# 18_LPDDR4_LPDDR4x_2.net
KiCad netlist of a schematic drawn in Altium Designer
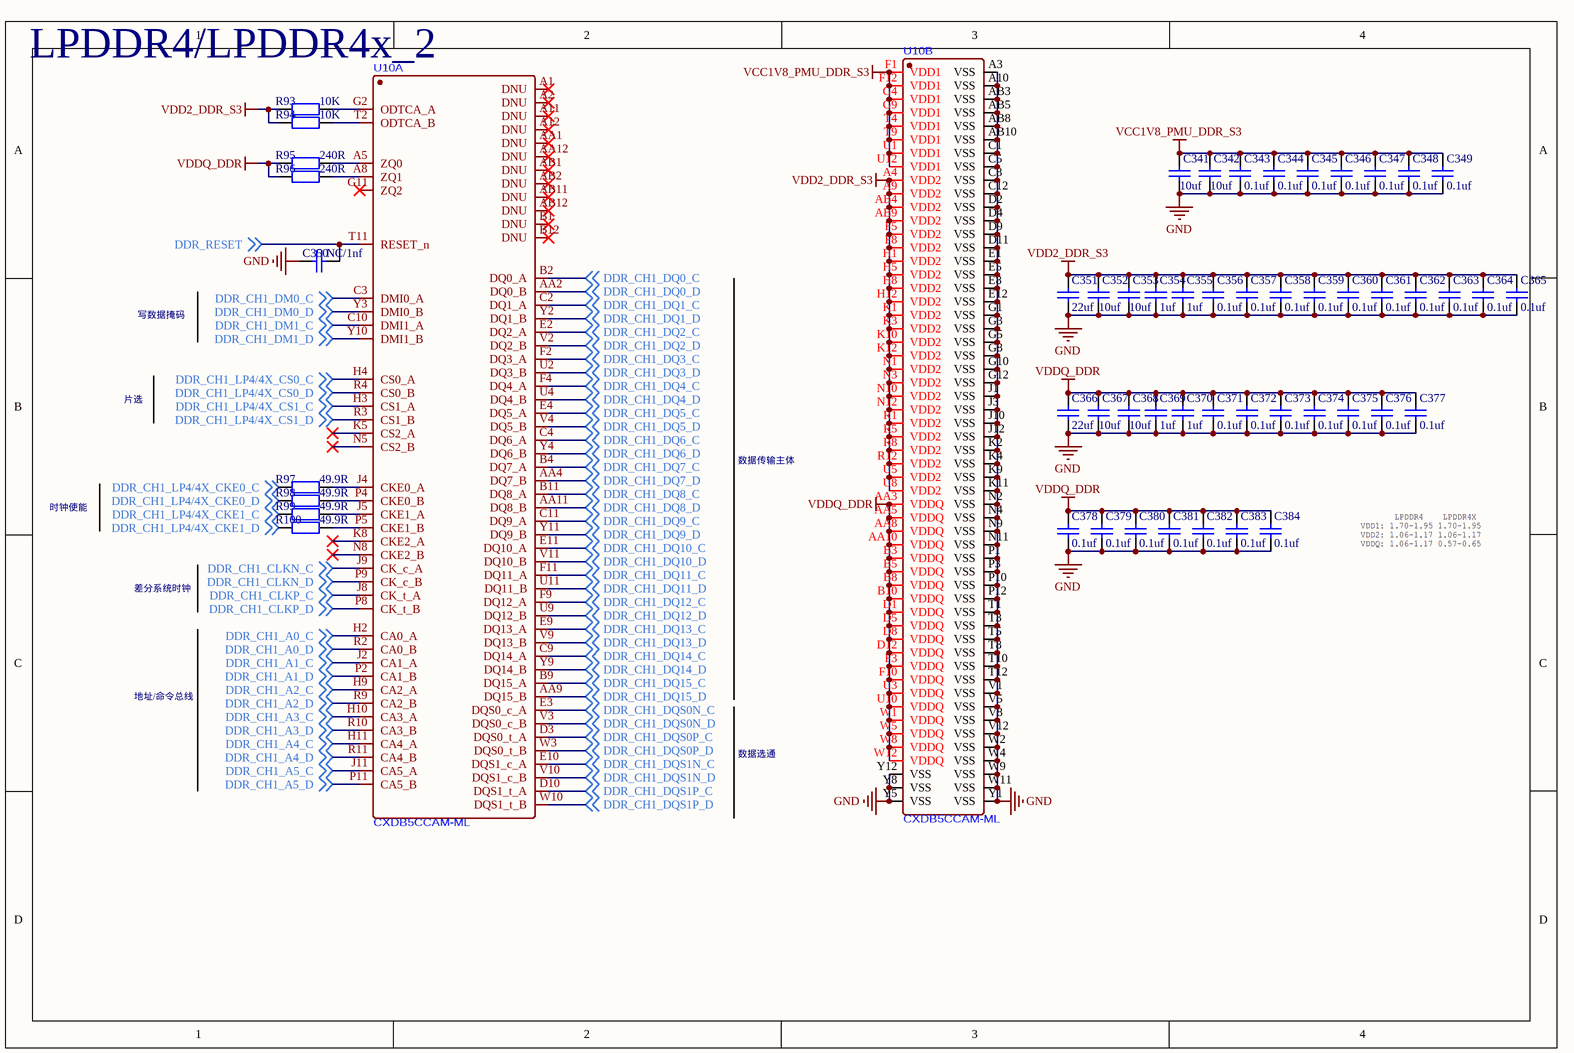
[diagram p0: 18.LPDDR4_LPDDR4x_2.SchDoc]

(export (version "E")
  (design (tool "Eeschema 10.0.6"))
  (components
    (comp (ref "C341")
      (value "10uf")
      (footprint "0.PCB1:C0402_L")
      (description "贴片电容/MLCC电容")
      (libsource (lib "RK3588") (part "C"))
    )
    (comp (ref "C342")
      (value "10uf")
      (footprint "0.PCB1:C0402_L")
      (description "贴片电容/MLCC电容")
      (libsource (lib "RK3588") (part "C"))
    )
    (comp (ref "C343")
      (value "0.1uf")
      (footprint "0.PCB1:C0201_L")
      (description "贴片电容/MLCC电容")
      (libsource (lib "RK3588") (part "C"))
    )
    (comp (ref "C344")
      (value "0.1uf")
      (footprint "0.PCB1:C0201_L")
      (description "贴片电容/MLCC电容")
      (libsource (lib "RK3588") (part "C"))
    )
    (comp (ref "C345")
      (value "0.1uf")
      (footprint "0.PCB1:C0201_L")
      (description "贴片电容/MLCC电容")
      (libsource (lib "RK3588") (part "C"))
    )
    (comp (ref "C346")
      (value "0.1uf")
      (footprint "0.PCB1:C0201_L")
      (description "贴片电容/MLCC电容")
      (libsource (lib "RK3588") (part "C"))
    )
    (comp (ref "C347")
      (value "0.1uf")
      (footprint "0.PCB1:C0201_L")
      (description "贴片电容/MLCC电容")
      (libsource (lib "RK3588") (part "C"))
    )
    (comp (ref "C348")
      (value "0.1uf")
      (footprint "0.PCB1:C0201_L")
      (description "贴片电容/MLCC电容")
      (libsource (lib "RK3588") (part "C"))
    )
    (comp (ref "C349")
      (value "0.1uf")
      (footprint "0.PCB1:C0201_L")
      (description "贴片电容/MLCC电容")
      (libsource (lib "RK3588") (part "C"))
    )
    (comp (ref "C350")
      (value "NC/1nf")
      (footprint "0.PCB1:C0201_L")
      (description "贴片电容/MLCC电容")
      (libsource (lib "RK3588") (part "C"))
    )
    (comp (ref "C351")
      (value "22uf")
      (footprint "0.PCB1:C0603_L")
      (description "贴片电容/MLCC电容")
      (libsource (lib "RK3588") (part "C"))
    )
    (comp (ref "C352")
      (value "10uf")
      (footprint "0.PCB1:C0402_L")
      (description "贴片电容/MLCC电容")
      (libsource (lib "RK3588") (part "C"))
    )
    (comp (ref "C353")
      (value "10uf")
      (footprint "0.PCB1:C0402_L")
      (description "贴片电容/MLCC电容")
      (libsource (lib "RK3588") (part "C"))
    )
    (comp (ref "C354")
      (value "1uf")
      (footprint "0.PCB1:C0201_L")
      (description "贴片电容/MLCC电容")
      (libsource (lib "RK3588") (part "C"))
    )
    (comp (ref "C355")
      (value "1uf")
      (footprint "0.PCB1:C0201_L")
      (description "贴片电容/MLCC电容")
      (libsource (lib "RK3588") (part "C"))
    )
    (comp (ref "C356")
      (value "0.1uf")
      (footprint "0.PCB1:C0201_L")
      (description "贴片电容/MLCC电容")
      (libsource (lib "RK3588") (part "C"))
    )
    (comp (ref "C357")
      (value "0.1uf")
      (footprint "0.PCB1:C0201_L")
      (description "贴片电容/MLCC电容")
      (libsource (lib "RK3588") (part "C"))
    )
    (comp (ref "C358")
      (value "0.1uf")
      (footprint "0.PCB1:C0201_L")
      (description "贴片电容/MLCC电容")
      (libsource (lib "RK3588") (part "C"))
    )
    (comp (ref "C359")
      (value "0.1uf")
      (footprint "0.PCB1:C0201_L")
      (description "贴片电容/MLCC电容")
      (libsource (lib "RK3588") (part "C"))
    )
    (comp (ref "C360")
      (value "0.1uf")
      (footprint "0.PCB1:C0201_L")
      (description "贴片电容/MLCC电容")
      (libsource (lib "RK3588") (part "C"))
    )
    (comp (ref "C361")
      (value "0.1uf")
      (footprint "0.PCB1:C0201_L")
      (description "贴片电容/MLCC电容")
      (libsource (lib "RK3588") (part "C"))
    )
    (comp (ref "C362")
      (value "0.1uf")
      (footprint "0.PCB1:C0201_L")
      (description "贴片电容/MLCC电容")
      (libsource (lib "RK3588") (part "C"))
    )
    (comp (ref "C363")
      (value "0.1uf")
      (footprint "0.PCB1:C0201_L")
      (description "贴片电容/MLCC电容")
      (libsource (lib "RK3588") (part "C"))
    )
    (comp (ref "C364")
      (value "0.1uf")
      (footprint "0.PCB1:C0201_L")
      (description "贴片电容/MLCC电容")
      (libsource (lib "RK3588") (part "C"))
    )
    (comp (ref "C365")
      (value "0.1uf")
      (footprint "0.PCB1:C0201_L")
      (description "贴片电容/MLCC电容")
      (libsource (lib "RK3588") (part "C"))
    )
    (comp (ref "C366")
      (value "22uf")
      (footprint "0.PCB1:C0603_L")
      (description "贴片电容/MLCC电容")
      (libsource (lib "RK3588") (part "C"))
    )
    (comp (ref "C367")
      (value "10uf")
      (footprint "0.PCB1:C0402_L")
      (description "贴片电容/MLCC电容")
      (libsource (lib "RK3588") (part "C"))
    )
    (comp (ref "C368")
      (value "10uf")
      (footprint "0.PCB1:C0402_L")
      (description "贴片电容/MLCC电容")
      (libsource (lib "RK3588") (part "C"))
    )
    (comp (ref "C369")
      (value "1uf")
      (footprint "0.PCB1:C0201_L")
      (description "贴片电容/MLCC电容")
      (libsource (lib "RK3588") (part "C"))
    )
    (comp (ref "C370")
      (value "1uf")
      (footprint "0.PCB1:C0201_L")
      (description "贴片电容/MLCC电容")
      (libsource (lib "RK3588") (part "C"))
    )
    (comp (ref "C371")
      (value "0.1uf")
      (footprint "0.PCB1:C0201_L")
      (description "贴片电容/MLCC电容")
      (libsource (lib "RK3588") (part "C"))
    )
    (comp (ref "C372")
      (value "0.1uf")
      (footprint "0.PCB1:C0201_L")
      (description "贴片电容/MLCC电容")
      (libsource (lib "RK3588") (part "C"))
    )
    (comp (ref "C373")
      (value "0.1uf")
      (footprint "0.PCB1:C0201_L")
      (description "贴片电容/MLCC电容")
      (libsource (lib "RK3588") (part "C"))
    )
    (comp (ref "C374")
      (value "0.1uf")
      (footprint "0.PCB1:C0201_L")
      (description "贴片电容/MLCC电容")
      (libsource (lib "RK3588") (part "C"))
    )
    (comp (ref "C375")
      (value "0.1uf")
      (footprint "0.PCB1:C0201_L")
      (description "贴片电容/MLCC电容")
      (libsource (lib "RK3588") (part "C"))
    )
    (comp (ref "C376")
      (value "0.1uf")
      (footprint "0.PCB1:C0201_L")
      (description "贴片电容/MLCC电容")
      (libsource (lib "RK3588") (part "C"))
    )
    (comp (ref "C377")
      (value "0.1uf")
      (footprint "0.PCB1:C0201_L")
      (description "贴片电容/MLCC电容")
      (libsource (lib "RK3588") (part "C"))
    )
    (comp (ref "C378")
      (value "0.1uf")
      (footprint "0.PCB1:C0201_L")
      (description "贴片电容/MLCC电容")
      (libsource (lib "RK3588") (part "C"))
    )
    (comp (ref "C379")
      (value "0.1uf")
      (footprint "0.PCB1:C0201_L")
      (description "贴片电容/MLCC电容")
      (libsource (lib "RK3588") (part "C"))
    )
    (comp (ref "C380")
      (value "0.1uf")
      (footprint "0.PCB1:C0201_L")
      (description "贴片电容/MLCC电容")
      (libsource (lib "RK3588") (part "C"))
    )
    (comp (ref "C381")
      (value "0.1uf")
      (footprint "0.PCB1:C0201_L")
      (description "贴片电容/MLCC电容")
      (libsource (lib "RK3588") (part "C"))
    )
    (comp (ref "C382")
      (value "0.1uf")
      (footprint "0.PCB1:C0201_L")
      (description "贴片电容/MLCC电容")
      (libsource (lib "RK3588") (part "C"))
    )
    (comp (ref "C383")
      (value "0.1uf")
      (footprint "0.PCB1:C0201_L")
      (description "贴片电容/MLCC电容")
      (libsource (lib "RK3588") (part "C"))
    )
    (comp (ref "C384")
      (value "0.1uf")
      (footprint "0.PCB1:C0201_L")
      (description "贴片电容/MLCC电容")
      (libsource (lib "RK3588") (part "C"))
    )
    (comp (ref "R93")
      (value "10K")
      (footprint "0.PCB1:R0201_L")
      (description "贴片电阻")
      (libsource (lib "RK3588") (part "R"))
    )
    (comp (ref "R94")
      (value "10K")
      (footprint "0.PCB1:R0201_L")
      (description "贴片电阻")
      (libsource (lib "RK3588") (part "R"))
    )
    (comp (ref "R95")
      (value "240R")
      (footprint "0.PCB1:R0201_L")
      (description "贴片电阻")
      (libsource (lib "RK3588") (part "R"))
    )
    (comp (ref "R96")
      (value "240R")
      (footprint "0.PCB1:R0201_L")
      (description "贴片电阻")
      (libsource (lib "RK3588") (part "R"))
    )
    (comp (ref "R97")
      (value "49.9R")
      (footprint "0.PCB1:R0201_L")
      (description "贴片电阻")
      (libsource (lib "RK3588") (part "R"))
    )
    (comp (ref "R98")
      (value "49.9R")
      (footprint "0.PCB1:R0201_L")
      (description "贴片电阻")
      (libsource (lib "RK3588") (part "R"))
    )
    (comp (ref "R99")
      (value "49.9R")
      (footprint "0.PCB1:R0201_L")
      (description "贴片电阻")
      (libsource (lib "RK3588") (part "R"))
    )
    (comp (ref "R100")
      (value "49.9R")
      (footprint "0.PCB1:R0201_L")
      (description "贴片电阻")
      (libsource (lib "RK3588") (part "R"))
    )
    (comp (ref "U10")
      (value "CXDB5CCAM-ML")
      (footprint "0.PCB1:FBGA-200_L15.0-W10.0-BL_K4F6E3S4HM")
      (libsource (lib "RK3588") (part "CXDB5CCAM-ML"))
    )
  )
  (nets
    (net (code "1") (name "DDR_CH1_A0_C") (class "Default")
      (node (ref "U10") (pin "H2") (pinfunction "CA0_A_H2") (pintype "passive"))
    )
    (net (code "2") (name "DDR_CH1_A0_D") (class "Default")
      (node (ref "U10") (pin "R2") (pinfunction "CA0_B_R2") (pintype "passive"))
    )
    (net (code "3") (name "DDR_CH1_A1_C") (class "Default")
      (node (ref "U10") (pin "J2") (pinfunction "CA1_A_J2") (pintype "passive"))
    )
    (net (code "4") (name "DDR_CH1_A1_D") (class "Default")
      (node (ref "U10") (pin "P2") (pinfunction "CA1_B_P2") (pintype "passive"))
    )
    (net (code "5") (name "DDR_CH1_A2_C") (class "Default")
      (node (ref "U10") (pin "H9") (pinfunction "CA2_A_H9") (pintype "passive"))
    )
    (net (code "6") (name "DDR_CH1_A2_D") (class "Default")
      (node (ref "U10") (pin "R9") (pinfunction "CA2_B_R9") (pintype "passive"))
    )
    (net (code "7") (name "DDR_CH1_A3_C") (class "Default")
      (node (ref "U10") (pin "H10") (pinfunction "CA3_A_H10") (pintype "passive"))
    )
    (net (code "8") (name "DDR_CH1_A3_D") (class "Default")
      (node (ref "U10") (pin "R10") (pinfunction "CA3_B_R10") (pintype "passive"))
    )
    (net (code "9") (name "DDR_CH1_A4_C") (class "Default")
      (node (ref "U10") (pin "H11") (pinfunction "CA4_A_H11") (pintype "passive"))
    )
    (net (code "10") (name "DDR_CH1_A4_D") (class "Default")
      (node (ref "U10") (pin "R11") (pinfunction "CA4_B_R11") (pintype "passive"))
    )
    (net (code "11") (name "DDR_CH1_A5_C") (class "Default")
      (node (ref "U10") (pin "J11") (pinfunction "CA5_A_J11") (pintype "passive"))
    )
    (net (code "12") (name "DDR_CH1_A5_D") (class "Default")
      (node (ref "U10") (pin "P11") (pinfunction "CA5_B_P11") (pintype "passive"))
    )
    (net (code "13") (name "DDR_CH1_CLKN_C") (class "Default")
      (node (ref "U10") (pin "J9") (pinfunction "CK_c_A_J9") (pintype "passive"))
    )
    (net (code "14") (name "DDR_CH1_CLKN_D") (class "Default")
      (node (ref "U10") (pin "P9") (pinfunction "CK_c_B_P9") (pintype "passive"))
    )
    (net (code "15") (name "DDR_CH1_CLKP_C") (class "Default")
      (node (ref "U10") (pin "J8") (pinfunction "CK_t_A_J8") (pintype "passive"))
    )
    (net (code "16") (name "DDR_CH1_CLKP_D") (class "Default")
      (node (ref "U10") (pin "P8") (pinfunction "CK_t_B_P8") (pintype "passive"))
    )
    (net (code "17") (name "DDR_CH1_DM0_C") (class "Default")
      (node (ref "U10") (pin "C3") (pinfunction "DMI0_A_C3") (pintype "passive"))
    )
    (net (code "18") (name "DDR_CH1_DM0_D") (class "Default")
      (node (ref "U10") (pin "Y3") (pinfunction "DMI0_B_Y3") (pintype "passive"))
    )
    (net (code "19") (name "DDR_CH1_DM1_C") (class "Default")
      (node (ref "U10") (pin "C10") (pinfunction "DMI1_A_C10") (pintype "passive"))
    )
    (net (code "20") (name "DDR_CH1_DM1_D") (class "Default")
      (node (ref "U10") (pin "Y10") (pinfunction "DMI1_B_Y10") (pintype "passive"))
    )
    (net (code "21") (name "DDR_CH1_DQ0_C") (class "Default")
      (node (ref "U10") (pin "B2") (pinfunction "DQ0_A_B2") (pintype "passive"))
    )
    (net (code "22") (name "DDR_CH1_DQ0_D") (class "Default")
      (node (ref "U10") (pin "AA2") (pinfunction "DQ0_B_AA2") (pintype "passive"))
    )
    (net (code "23") (name "DDR_CH1_DQ1_C") (class "Default")
      (node (ref "U10") (pin "C2") (pinfunction "DQ1_A_C2") (pintype "passive"))
    )
    (net (code "24") (name "DDR_CH1_DQ1_D") (class "Default")
      (node (ref "U10") (pin "Y2") (pinfunction "DQ1_B_Y2") (pintype "passive"))
    )
    (net (code "25") (name "DDR_CH1_DQ2_C") (class "Default")
      (node (ref "U10") (pin "E2") (pinfunction "DQ2_A_E2") (pintype "passive"))
    )
    (net (code "26") (name "DDR_CH1_DQ2_D") (class "Default")
      (node (ref "U10") (pin "V2") (pinfunction "DQ2_B_V2") (pintype "passive"))
    )
    (net (code "27") (name "DDR_CH1_DQ3_C") (class "Default")
      (node (ref "U10") (pin "F2") (pinfunction "DQ3_A_F2") (pintype "passive"))
    )
    (net (code "28") (name "DDR_CH1_DQ3_D") (class "Default")
      (node (ref "U10") (pin "U2") (pinfunction "DQ3_B_U2") (pintype "passive"))
    )
    (net (code "29") (name "DDR_CH1_DQ4_C") (class "Default")
      (node (ref "U10") (pin "F4") (pinfunction "DQ4_A_F4") (pintype "passive"))
    )
    (net (code "30") (name "DDR_CH1_DQ4_D") (class "Default")
      (node (ref "U10") (pin "U4") (pinfunction "DQ4_B_U4") (pintype "passive"))
    )
    (net (code "31") (name "DDR_CH1_DQ5_C") (class "Default")
      (node (ref "U10") (pin "E4") (pinfunction "DQ5_A_E4") (pintype "passive"))
    )
    (net (code "32") (name "DDR_CH1_DQ5_D") (class "Default")
      (node (ref "U10") (pin "V4") (pinfunction "DQ5_B_V4") (pintype "passive"))
    )
    (net (code "33") (name "DDR_CH1_DQ6_C") (class "Default")
      (node (ref "U10") (pin "C4") (pinfunction "DQ6_A_C4") (pintype "passive"))
    )
    (net (code "34") (name "DDR_CH1_DQ6_D") (class "Default")
      (node (ref "U10") (pin "Y4") (pinfunction "DQ6_B_Y4") (pintype "passive"))
    )
    (net (code "35") (name "DDR_CH1_DQ7_C") (class "Default")
      (node (ref "U10") (pin "B4") (pinfunction "DQ7_A_B4") (pintype "passive"))
    )
    (net (code "36") (name "DDR_CH1_DQ7_D") (class "Default")
      (node (ref "U10") (pin "AA4") (pinfunction "DQ7_B_AA4") (pintype "passive"))
    )
    (net (code "37") (name "DDR_CH1_DQ8_C") (class "Default")
      (node (ref "U10") (pin "B11") (pinfunction "DQ8_A_B11") (pintype "passive"))
    )
    (net (code "38") (name "DDR_CH1_DQ8_D") (class "Default")
      (node (ref "U10") (pin "AA11") (pinfunction "DQ8_B_AA11") (pintype "passive"))
    )
    (net (code "39") (name "DDR_CH1_DQ9_C") (class "Default")
      (node (ref "U10") (pin "C11") (pinfunction "DQ9_A_C11") (pintype "passive"))
    )
    (net (code "40") (name "DDR_CH1_DQ9_D") (class "Default")
      (node (ref "U10") (pin "Y11") (pinfunction "DQ9_B_Y11") (pintype "passive"))
    )
    (net (code "41") (name "DDR_CH1_DQ10_C") (class "Default")
      (node (ref "U10") (pin "E11") (pinfunction "DQ10_A_E11") (pintype "passive"))
    )
    (net (code "42") (name "DDR_CH1_DQ10_D") (class "Default")
      (node (ref "U10") (pin "V11") (pinfunction "DQ10_B_V11") (pintype "passive"))
    )
    (net (code "43") (name "DDR_CH1_DQ11_C") (class "Default")
      (node (ref "U10") (pin "F11") (pinfunction "DQ11_A_F11") (pintype "passive"))
    )
    (net (code "44") (name "DDR_CH1_DQ11_D") (class "Default")
      (node (ref "U10") (pin "U11") (pinfunction "DQ11_B_U11") (pintype "passive"))
    )
    (net (code "45") (name "DDR_CH1_DQ12_C") (class "Default")
      (node (ref "U10") (pin "F9") (pinfunction "DQ12_A_F9") (pintype "passive"))
    )
    (net (code "46") (name "DDR_CH1_DQ12_D") (class "Default")
      (node (ref "U10") (pin "U9") (pinfunction "DQ12_B_U9") (pintype "passive"))
    )
    (net (code "47") (name "DDR_CH1_DQ13_C") (class "Default")
      (node (ref "U10") (pin "E9") (pinfunction "DQ13_A_E9") (pintype "passive"))
    )
    (net (code "48") (name "DDR_CH1_DQ13_D") (class "Default")
      (node (ref "U10") (pin "V9") (pinfunction "DQ13_B_V9") (pintype "passive"))
    )
    (net (code "49") (name "DDR_CH1_DQ14_C") (class "Default")
      (node (ref "U10") (pin "C9") (pinfunction "DQ14_A_C9") (pintype "passive"))
    )
    (net (code "50") (name "DDR_CH1_DQ14_D") (class "Default")
      (node (ref "U10") (pin "Y9") (pinfunction "DQ14_B_Y9") (pintype "passive"))
    )
    (net (code "51") (name "DDR_CH1_DQ15_C") (class "Default")
      (node (ref "U10") (pin "B9") (pinfunction "DQ15_A_B9") (pintype "passive"))
    )
    (net (code "52") (name "DDR_CH1_DQ15_D") (class "Default")
      (node (ref "U10") (pin "AA9") (pinfunction "DQ15_B_AA9") (pintype "passive"))
    )
    (net (code "53") (name "DDR_CH1_DQS0N_C") (class "Default")
      (node (ref "U10") (pin "E3") (pinfunction "DQS0_c_A_E3") (pintype "passive"))
    )
    (net (code "54") (name "DDR_CH1_DQS0N_D") (class "Default")
      (node (ref "U10") (pin "V3") (pinfunction "DQS0_c_B_V3") (pintype "passive"))
    )
    (net (code "55") (name "DDR_CH1_DQS0P_C") (class "Default")
      (node (ref "U10") (pin "D3") (pinfunction "DQS0_t_A_D3") (pintype "passive"))
    )
    (net (code "56") (name "DDR_CH1_DQS0P_D") (class "Default")
      (node (ref "U10") (pin "W3") (pinfunction "DQS0_t_B_W3") (pintype "passive"))
    )
    (net (code "57") (name "DDR_CH1_DQS1N_C") (class "Default")
      (node (ref "U10") (pin "E10") (pinfunction "DQS1_c_A_E10") (pintype "passive"))
    )
    (net (code "58") (name "DDR_CH1_DQS1N_D") (class "Default")
      (node (ref "U10") (pin "V10") (pinfunction "DQS1_c_B_V10") (pintype "passive"))
    )
    (net (code "59") (name "DDR_CH1_DQS1P_C") (class "Default")
      (node (ref "U10") (pin "D10") (pinfunction "DQS1_t_A_D10") (pintype "passive"))
    )
    (net (code "60") (name "DDR_CH1_DQS1P_D") (class "Default")
      (node (ref "U10") (pin "W10") (pinfunction "DQS1_t_B_W10") (pintype "passive"))
    )
    (net (code "61") (name "DDR_CH1_LP4{slash}4X_CKE0_C") (class "Default")
      (node (ref "R97") (pin "1") (pinfunction "1_1") (pintype "passive"))
    )
    (net (code "62") (name "DDR_CH1_LP4{slash}4X_CKE0_D") (class "Default")
      (node (ref "R98") (pin "1") (pinfunction "1_1") (pintype "passive"))
    )
    (net (code "63") (name "DDR_CH1_LP4{slash}4X_CKE1_C") (class "Default")
      (node (ref "R99") (pin "1") (pinfunction "1_1") (pintype "passive"))
    )
    (net (code "64") (name "DDR_CH1_LP4{slash}4X_CKE1_D") (class "Default")
      (node (ref "R100") (pin "1") (pinfunction "1_1") (pintype "passive"))
    )
    (net (code "65") (name "DDR_CH1_LP4{slash}4X_CS0_C") (class "Default")
      (node (ref "U10") (pin "H4") (pinfunction "CS0_A_H4") (pintype "passive"))
    )
    (net (code "66") (name "DDR_CH1_LP4{slash}4X_CS0_D") (class "Default")
      (node (ref "U10") (pin "R4") (pinfunction "CS0_B_R4") (pintype "passive"))
    )
    (net (code "67") (name "DDR_CH1_LP4{slash}4X_CS1_C") (class "Default")
      (node (ref "U10") (pin "H3") (pinfunction "CS1_A_H3") (pintype "passive"))
    )
    (net (code "68") (name "DDR_CH1_LP4{slash}4X_CS1_D") (class "Default")
      (node (ref "U10") (pin "R3") (pinfunction "CS1_B_R3") (pintype "passive"))
    )
    (net (code "69") (name "DDR_RESET") (class "Default")
      (node (ref "C350") (pin "2") (pinfunction "2_2") (pintype "passive"))
      (node (ref "U10") (pin "T11") (pinfunction "RESET_n_T11") (pintype "passive"))
    )
    (net (code "70") (name "GND") (class "Default")
      (node (ref "C341") (pin "1") (pinfunction "1_1") (pintype "passive"))
      (node (ref "C342") (pin "1") (pinfunction "1_1") (pintype "passive"))
      (node (ref "C343") (pin "1") (pinfunction "1_1") (pintype "passive"))
      (node (ref "C344") (pin "1") (pinfunction "1_1") (pintype "passive"))
      (node (ref "C345") (pin "1") (pinfunction "1_1") (pintype "passive"))
      (node (ref "C346") (pin "1") (pinfunction "1_1") (pintype "passive"))
      (node (ref "C347") (pin "1") (pinfunction "1_1") (pintype "passive"))
      (node (ref "C348") (pin "1") (pinfunction "1_1") (pintype "passive"))
      (node (ref "C349") (pin "1") (pinfunction "1_1") (pintype "passive"))
      (node (ref "C350") (pin "1") (pinfunction "1_1") (pintype "passive"))
      (node (ref "C351") (pin "1") (pinfunction "1_1") (pintype "passive"))
      (node (ref "C352") (pin "1") (pinfunction "1_1") (pintype "passive"))
      (node (ref "C353") (pin "1") (pinfunction "1_1") (pintype "passive"))
      (node (ref "C354") (pin "1") (pinfunction "1_1") (pintype "passive"))
      (node (ref "C355") (pin "1") (pinfunction "1_1") (pintype "passive"))
      (node (ref "C356") (pin "1") (pinfunction "1_1") (pintype "passive"))
      (node (ref "C357") (pin "1") (pinfunction "1_1") (pintype "passive"))
      (node (ref "C358") (pin "1") (pinfunction "1_1") (pintype "passive"))
      (node (ref "C359") (pin "1") (pinfunction "1_1") (pintype "passive"))
      (node (ref "C360") (pin "1") (pinfunction "1_1") (pintype "passive"))
      (node (ref "C361") (pin "1") (pinfunction "1_1") (pintype "passive"))
      (node (ref "C362") (pin "1") (pinfunction "1_1") (pintype "passive"))
      (node (ref "C363") (pin "1") (pinfunction "1_1") (pintype "passive"))
      (node (ref "C364") (pin "1") (pinfunction "1_1") (pintype "passive"))
      (node (ref "C365") (pin "1") (pinfunction "1_1") (pintype "passive"))
      (node (ref "C366") (pin "1") (pinfunction "1_1") (pintype "passive"))
      (node (ref "C367") (pin "1") (pinfunction "1_1") (pintype "passive"))
      (node (ref "C368") (pin "1") (pinfunction "1_1") (pintype "passive"))
      (node (ref "C369") (pin "1") (pinfunction "1_1") (pintype "passive"))
      (node (ref "C370") (pin "1") (pinfunction "1_1") (pintype "passive"))
      (node (ref "C371") (pin "1") (pinfunction "1_1") (pintype "passive"))
      (node (ref "C372") (pin "1") (pinfunction "1_1") (pintype "passive"))
      (node (ref "C373") (pin "1") (pinfunction "1_1") (pintype "passive"))
      (node (ref "C374") (pin "1") (pinfunction "1_1") (pintype "passive"))
      (node (ref "C375") (pin "1") (pinfunction "1_1") (pintype "passive"))
      (node (ref "C376") (pin "1") (pinfunction "1_1") (pintype "passive"))
      (node (ref "C377") (pin "1") (pinfunction "1_1") (pintype "passive"))
      (node (ref "C378") (pin "1") (pinfunction "1_1") (pintype "passive"))
      (node (ref "C379") (pin "1") (pinfunction "1_1") (pintype "passive"))
      (node (ref "C380") (pin "1") (pinfunction "1_1") (pintype "passive"))
      (node (ref "C381") (pin "1") (pinfunction "1_1") (pintype "passive"))
      (node (ref "C382") (pin "1") (pinfunction "1_1") (pintype "passive"))
      (node (ref "C383") (pin "1") (pinfunction "1_1") (pintype "passive"))
      (node (ref "C384") (pin "1") (pinfunction "1_1") (pintype "passive"))
      (node (ref "U10") (pin "A10") (pinfunction "VSS_A10") (pintype "passive"))
      (node (ref "U10") (pin "A3") (pinfunction "VSS_A3") (pintype "passive"))
      (node (ref "U10") (pin "AB10") (pinfunction "VSS_AB10") (pintype "passive"))
      (node (ref "U10") (pin "AB3") (pinfunction "VSS_AB3") (pintype "passive"))
      (node (ref "U10") (pin "AB5") (pinfunction "VSS_AB5") (pintype "passive"))
      (node (ref "U10") (pin "AB8") (pinfunction "VSS_AB8") (pintype "passive"))
      (node (ref "U10") (pin "C1") (pinfunction "VSS_C1") (pintype "passive"))
      (node (ref "U10") (pin "C12") (pinfunction "VSS_C12") (pintype "passive"))
      (node (ref "U10") (pin "C5") (pinfunction "VSS_C5") (pintype "passive"))
      (node (ref "U10") (pin "C8") (pinfunction "VSS_C8") (pintype "passive"))
      (node (ref "U10") (pin "D11") (pinfunction "VSS_D11") (pintype "passive"))
      (node (ref "U10") (pin "D2") (pinfunction "VSS_D2") (pintype "passive"))
      (node (ref "U10") (pin "D4") (pinfunction "VSS_D4") (pintype "passive"))
      (node (ref "U10") (pin "D9") (pinfunction "VSS_D9") (pintype "passive"))
      (node (ref "U10") (pin "E1") (pinfunction "VSS_E1") (pintype "passive"))
      (node (ref "U10") (pin "E12") (pinfunction "VSS_E12") (pintype "passive"))
      (node (ref "U10") (pin "E5") (pinfunction "VSS_E5") (pintype "passive"))
      (node (ref "U10") (pin "E8") (pinfunction "VSS_E8") (pintype "passive"))
      (node (ref "U10") (pin "G1") (pinfunction "VSS_G1") (pintype "passive"))
      (node (ref "U10") (pin "G10") (pinfunction "VSS_G10") (pintype "passive"))
      (node (ref "U10") (pin "G12") (pinfunction "VSS_G12") (pintype "passive"))
      (node (ref "U10") (pin "G3") (pinfunction "VSS_G3") (pintype "passive"))
      (node (ref "U10") (pin "G5") (pinfunction "VSS_G5") (pintype "passive"))
      (node (ref "U10") (pin "G8") (pinfunction "VSS_G8") (pintype "passive"))
      (node (ref "U10") (pin "J1") (pinfunction "VSS_J1") (pintype "passive"))
      (node (ref "U10") (pin "J10") (pinfunction "VSS_J10") (pintype "passive"))
      (node (ref "U10") (pin "J12") (pinfunction "VSS_J12") (pintype "passive"))
      (node (ref "U10") (pin "J3") (pinfunction "VSS_J3") (pintype "passive"))
      (node (ref "U10") (pin "K11") (pinfunction "VSS_K11") (pintype "passive"))
      (node (ref "U10") (pin "K2") (pinfunction "VSS_K2") (pintype "passive"))
      (node (ref "U10") (pin "K4") (pinfunction "VSS_K4") (pintype "passive"))
      (node (ref "U10") (pin "K9") (pinfunction "VSS_K9") (pintype "passive"))
      (node (ref "U10") (pin "N11") (pinfunction "VSS_N11") (pintype "passive"))
      (node (ref "U10") (pin "N2") (pinfunction "VSS_N2") (pintype "passive"))
      (node (ref "U10") (pin "N4") (pinfunction "VSS_N4") (pintype "passive"))
      (node (ref "U10") (pin "N9") (pinfunction "VSS_N9") (pintype "passive"))
      (node (ref "U10") (pin "P1") (pinfunction "VSS_P1") (pintype "passive"))
      (node (ref "U10") (pin "P10") (pinfunction "VSS_P10") (pintype "passive"))
      (node (ref "U10") (pin "P12") (pinfunction "VSS_P12") (pintype "passive"))
      (node (ref "U10") (pin "P3") (pinfunction "VSS_P3") (pintype "passive"))
      (node (ref "U10") (pin "T1") (pinfunction "VSS_T1") (pintype "passive"))
      (node (ref "U10") (pin "T10") (pinfunction "VSS_T10") (pintype "passive"))
      (node (ref "U10") (pin "T12") (pinfunction "VSS_T12") (pintype "passive"))
      (node (ref "U10") (pin "T3") (pinfunction "VSS_T3") (pintype "passive"))
      (node (ref "U10") (pin "T5") (pinfunction "VSS_T5") (pintype "passive"))
      (node (ref "U10") (pin "T8") (pinfunction "VSS_T8") (pintype "passive"))
      (node (ref "U10") (pin "V1") (pinfunction "VSS_V1") (pintype "passive"))
      (node (ref "U10") (pin "V12") (pinfunction "VSS_V12") (pintype "passive"))
      (node (ref "U10") (pin "V5") (pinfunction "VSS_V5") (pintype "passive"))
      (node (ref "U10") (pin "V8") (pinfunction "VSS_V8") (pintype "passive"))
      (node (ref "U10") (pin "W11") (pinfunction "VSS_W11") (pintype "passive"))
      (node (ref "U10") (pin "W2") (pinfunction "VSS_W2") (pintype "passive"))
      (node (ref "U10") (pin "W4") (pinfunction "VSS_W4") (pintype "passive"))
      (node (ref "U10") (pin "W9") (pinfunction "VSS_W9") (pintype "passive"))
      (node (ref "U10") (pin "Y1") (pinfunction "VSS_Y1") (pintype "passive"))
      (node (ref "U10") (pin "Y12") (pinfunction "VSS_Y12") (pintype "passive"))
      (node (ref "U10") (pin "Y5") (pinfunction "VSS_Y5") (pintype "passive"))
      (node (ref "U10") (pin "Y8") (pinfunction "VSS_Y8") (pintype "passive"))
    )
    (net (code "71") (name "Net-(U10A-CKE0_A)") (class "Default")
      (node (ref "R97") (pin "2") (pinfunction "2_2") (pintype "passive"))
      (node (ref "U10") (pin "J4") (pinfunction "CKE0_A_J4") (pintype "passive"))
    )
    (net (code "72") (name "Net-(U10A-CKE0_B)") (class "Default")
      (node (ref "R98") (pin "2") (pinfunction "2_2") (pintype "passive"))
      (node (ref "U10") (pin "P4") (pinfunction "CKE0_B_P4") (pintype "passive"))
    )
    (net (code "73") (name "Net-(U10A-CKE1_A)") (class "Default")
      (node (ref "R99") (pin "2") (pinfunction "2_2") (pintype "passive"))
      (node (ref "U10") (pin "J5") (pinfunction "CKE1_A_J5") (pintype "passive"))
    )
    (net (code "74") (name "Net-(U10A-CKE1_B)") (class "Default")
      (node (ref "R100") (pin "2") (pinfunction "2_2") (pintype "passive"))
      (node (ref "U10") (pin "P5") (pinfunction "CKE1_B_P5") (pintype "passive"))
    )
    (net (code "75") (name "Net-(U10A-ODTCA_A)") (class "Default")
      (node (ref "R93") (pin "2") (pinfunction "2_2") (pintype "passive"))
      (node (ref "U10") (pin "G2") (pinfunction "ODTCA_A_G2") (pintype "passive"))
    )
    (net (code "76") (name "Net-(U10A-ODTCA_B)") (class "Default")
      (node (ref "R94") (pin "2") (pinfunction "2_2") (pintype "passive"))
      (node (ref "U10") (pin "T2") (pinfunction "ODTCA_B_T2") (pintype "passive"))
    )
    (net (code "77") (name "Net-(U10A-ZQ0)") (class "Default")
      (node (ref "R95") (pin "2") (pinfunction "2_2") (pintype "passive"))
      (node (ref "U10") (pin "A5") (pinfunction "ZQ0_A5") (pintype "passive"))
    )
    (net (code "78") (name "Net-(U10A-ZQ1)") (class "Default")
      (node (ref "R96") (pin "2") (pinfunction "2_2") (pintype "passive"))
      (node (ref "U10") (pin "A8") (pinfunction "ZQ1_A8") (pintype "passive"))
    )
    (net (code "79") (name "VCC1V8_PMU_DDR_S3") (class "Default")
      (node (ref "C341") (pin "2") (pinfunction "2_2") (pintype "passive"))
      (node (ref "C342") (pin "2") (pinfunction "2_2") (pintype "passive"))
      (node (ref "C343") (pin "2") (pinfunction "2_2") (pintype "passive"))
      (node (ref "C344") (pin "2") (pinfunction "2_2") (pintype "passive"))
      (node (ref "C345") (pin "2") (pinfunction "2_2") (pintype "passive"))
      (node (ref "C346") (pin "2") (pinfunction "2_2") (pintype "passive"))
      (node (ref "C347") (pin "2") (pinfunction "2_2") (pintype "passive"))
      (node (ref "C348") (pin "2") (pinfunction "2_2") (pintype "passive"))
      (node (ref "C349") (pin "2") (pinfunction "2_2") (pintype "passive"))
      (node (ref "U10") (pin "F1") (pinfunction "VDD1_F1") (pintype "passive"))
      (node (ref "U10") (pin "F12") (pinfunction "VDD1_F12") (pintype "passive"))
      (node (ref "U10") (pin "G4") (pinfunction "VDD1_G4") (pintype "passive"))
      (node (ref "U10") (pin "G9") (pinfunction "VDD1_G9") (pintype "passive"))
      (node (ref "U10") (pin "T4") (pinfunction "VDD1_T4") (pintype "passive"))
      (node (ref "U10") (pin "T9") (pinfunction "VDD1_T9") (pintype "passive"))
      (node (ref "U10") (pin "U1") (pinfunction "VDD1_U1") (pintype "passive"))
      (node (ref "U10") (pin "U12") (pinfunction "VDD1_U12") (pintype "passive"))
    )
    (net (code "80") (name "VDD2_DDR_S3") (class "Default")
      (node (ref "C351") (pin "2") (pinfunction "2_2") (pintype "passive"))
      (node (ref "C352") (pin "2") (pinfunction "2_2") (pintype "passive"))
      (node (ref "C353") (pin "2") (pinfunction "2_2") (pintype "passive"))
      (node (ref "C354") (pin "2") (pinfunction "2_2") (pintype "passive"))
      (node (ref "C355") (pin "2") (pinfunction "2_2") (pintype "passive"))
      (node (ref "C356") (pin "2") (pinfunction "2_2") (pintype "passive"))
      (node (ref "C357") (pin "2") (pinfunction "2_2") (pintype "passive"))
      (node (ref "C358") (pin "2") (pinfunction "2_2") (pintype "passive"))
      (node (ref "C359") (pin "2") (pinfunction "2_2") (pintype "passive"))
      (node (ref "C360") (pin "2") (pinfunction "2_2") (pintype "passive"))
      (node (ref "C361") (pin "2") (pinfunction "2_2") (pintype "passive"))
      (node (ref "C362") (pin "2") (pinfunction "2_2") (pintype "passive"))
      (node (ref "C363") (pin "2") (pinfunction "2_2") (pintype "passive"))
      (node (ref "C364") (pin "2") (pinfunction "2_2") (pintype "passive"))
      (node (ref "C365") (pin "2") (pinfunction "2_2") (pintype "passive"))
      (node (ref "R93") (pin "1") (pinfunction "1_1") (pintype "passive"))
      (node (ref "R94") (pin "1") (pinfunction "1_1") (pintype "passive"))
      (node (ref "U10") (pin "A4") (pinfunction "VDD2_A4") (pintype "passive"))
      (node (ref "U10") (pin "A9") (pinfunction "VDD2_A9") (pintype "passive"))
      (node (ref "U10") (pin "AB4") (pinfunction "VDD2_AB4") (pintype "passive"))
      (node (ref "U10") (pin "AB9") (pinfunction "VDD2_AB9") (pintype "passive"))
      (node (ref "U10") (pin "F5") (pinfunction "VDD2_F5") (pintype "passive"))
      (node (ref "U10") (pin "F8") (pinfunction "VDD2_F8") (pintype "passive"))
      (node (ref "U10") (pin "H1") (pinfunction "VDD2_H1") (pintype "passive"))
      (node (ref "U10") (pin "H12") (pinfunction "VDD2_H12") (pintype "passive"))
      (node (ref "U10") (pin "H5") (pinfunction "VDD2_H5") (pintype "passive"))
      (node (ref "U10") (pin "H8") (pinfunction "VDD2_H8") (pintype "passive"))
      (node (ref "U10") (pin "K1") (pinfunction "VDD2_K1") (pintype "passive"))
      (node (ref "U10") (pin "K10") (pinfunction "VDD2_K10") (pintype "passive"))
      (node (ref "U10") (pin "K12") (pinfunction "VDD2_K12") (pintype "passive"))
      (node (ref "U10") (pin "K3") (pinfunction "VDD2_K3") (pintype "passive"))
      (node (ref "U10") (pin "N1") (pinfunction "VDD2_N1") (pintype "passive"))
      (node (ref "U10") (pin "N10") (pinfunction "VDD2_N10") (pintype "passive"))
      (node (ref "U10") (pin "N12") (pinfunction "VDD2_N12") (pintype "passive"))
      (node (ref "U10") (pin "N3") (pinfunction "VDD2_N3") (pintype "passive"))
      (node (ref "U10") (pin "R1") (pinfunction "VDD2_R1") (pintype "passive"))
      (node (ref "U10") (pin "R12") (pinfunction "VDD2_R12") (pintype "passive"))
      (node (ref "U10") (pin "R5") (pinfunction "VDD2_R5") (pintype "passive"))
      (node (ref "U10") (pin "R8") (pinfunction "VDD2_R8") (pintype "passive"))
      (node (ref "U10") (pin "U5") (pinfunction "VDD2_U5") (pintype "passive"))
      (node (ref "U10") (pin "U8") (pinfunction "VDD2_U8") (pintype "passive"))
    )
    (net (code "81") (name "VDDQ_DDR") (class "Default")
      (node (ref "C366") (pin "2") (pinfunction "2_2") (pintype "passive"))
      (node (ref "C367") (pin "2") (pinfunction "2_2") (pintype "passive"))
      (node (ref "C368") (pin "2") (pinfunction "2_2") (pintype "passive"))
      (node (ref "C369") (pin "2") (pinfunction "2_2") (pintype "passive"))
      (node (ref "C370") (pin "2") (pinfunction "2_2") (pintype "passive"))
      (node (ref "C371") (pin "2") (pinfunction "2_2") (pintype "passive"))
      (node (ref "C372") (pin "2") (pinfunction "2_2") (pintype "passive"))
      (node (ref "C373") (pin "2") (pinfunction "2_2") (pintype "passive"))
      (node (ref "C374") (pin "2") (pinfunction "2_2") (pintype "passive"))
      (node (ref "C375") (pin "2") (pinfunction "2_2") (pintype "passive"))
      (node (ref "C376") (pin "2") (pinfunction "2_2") (pintype "passive"))
      (node (ref "C377") (pin "2") (pinfunction "2_2") (pintype "passive"))
      (node (ref "C378") (pin "2") (pinfunction "2_2") (pintype "passive"))
      (node (ref "C379") (pin "2") (pinfunction "2_2") (pintype "passive"))
      (node (ref "C380") (pin "2") (pinfunction "2_2") (pintype "passive"))
      (node (ref "C381") (pin "2") (pinfunction "2_2") (pintype "passive"))
      (node (ref "C382") (pin "2") (pinfunction "2_2") (pintype "passive"))
      (node (ref "C383") (pin "2") (pinfunction "2_2") (pintype "passive"))
      (node (ref "C384") (pin "2") (pinfunction "2_2") (pintype "passive"))
      (node (ref "R95") (pin "1") (pinfunction "1_1") (pintype "passive"))
      (node (ref "R96") (pin "1") (pinfunction "1_1") (pintype "passive"))
      (node (ref "U10") (pin "AA10") (pinfunction "VDDQ_AA10") (pintype "passive"))
      (node (ref "U10") (pin "AA3") (pinfunction "VDDQ_AA3") (pintype "passive"))
      (node (ref "U10") (pin "AA5") (pinfunction "VDDQ_AA5") (pintype "passive"))
      (node (ref "U10") (pin "AA8") (pinfunction "VDDQ_AA8") (pintype "passive"))
      (node (ref "U10") (pin "B10") (pinfunction "VDDQ_B10") (pintype "passive"))
      (node (ref "U10") (pin "B3") (pinfunction "VDDQ_B3") (pintype "passive"))
      (node (ref "U10") (pin "B5") (pinfunction "VDDQ_B5") (pintype "passive"))
      (node (ref "U10") (pin "B8") (pinfunction "VDDQ_B8") (pintype "passive"))
      (node (ref "U10") (pin "D1") (pinfunction "VDDQ_D1") (pintype "passive"))
      (node (ref "U10") (pin "D12") (pinfunction "VDDQ_D12") (pintype "passive"))
      (node (ref "U10") (pin "D5") (pinfunction "VDDQ_D5") (pintype "passive"))
      (node (ref "U10") (pin "D8") (pinfunction "VDDQ_D8") (pintype "passive"))
      (node (ref "U10") (pin "F10") (pinfunction "VDDQ_F10") (pintype "passive"))
      (node (ref "U10") (pin "F3") (pinfunction "VDDQ_F3") (pintype "passive"))
      (node (ref "U10") (pin "U10") (pinfunction "VDDQ_U10") (pintype "passive"))
      (node (ref "U10") (pin "U3") (pinfunction "VDDQ_U3") (pintype "passive"))
      (node (ref "U10") (pin "W1") (pinfunction "VDDQ_W1") (pintype "passive"))
      (node (ref "U10") (pin "W12") (pinfunction "VDDQ_W12") (pintype "passive"))
      (node (ref "U10") (pin "W5") (pinfunction "VDDQ_W5") (pintype "passive"))
      (node (ref "U10") (pin "W8") (pinfunction "VDDQ_W8") (pintype "passive"))
    )
    (net (code "82") (name "unconnected-(U10A-CKE2_A-PadK8)") (class "Default")
      (node (ref "U10") (pin "K8") (pinfunction "CKE2_A_K8") (pintype "passive+no_connect"))
    )
    (net (code "83") (name "unconnected-(U10A-CKE2_B-PadN8)") (class "Default")
      (node (ref "U10") (pin "N8") (pinfunction "CKE2_B_N8") (pintype "passive+no_connect"))
    )
    (net (code "84") (name "unconnected-(U10A-CS2_A-PadK5)") (class "Default")
      (node (ref "U10") (pin "K5") (pinfunction "CS2_A_K5") (pintype "passive+no_connect"))
    )
    (net (code "85") (name "unconnected-(U10A-CS2_B-PadN5)") (class "Default")
      (node (ref "U10") (pin "N5") (pinfunction "CS2_B_N5") (pintype "passive+no_connect"))
    )
    (net (code "86") (name "unconnected-(U10A-DNU-PadA1)") (class "Default")
      (node (ref "U10") (pin "A1") (pinfunction "DNU_A1") (pintype "passive+no_connect"))
    )
    (net (code "87") (name "unconnected-(U10A-DNU-PadA2)") (class "Default")
      (node (ref "U10") (pin "A2") (pinfunction "DNU_A2") (pintype "passive+no_connect"))
    )
    (net (code "88") (name "unconnected-(U10A-DNU-PadA11)") (class "Default")
      (node (ref "U10") (pin "A11") (pinfunction "DNU_A11") (pintype "passive+no_connect"))
    )
    (net (code "89") (name "unconnected-(U10A-DNU-PadA12)") (class "Default")
      (node (ref "U10") (pin "A12") (pinfunction "DNU_A12") (pintype "passive+no_connect"))
    )
    (net (code "90") (name "unconnected-(U10A-DNU-PadAA1)") (class "Default")
      (node (ref "U10") (pin "AA1") (pinfunction "DNU_AA1") (pintype "passive+no_connect"))
    )
    (net (code "91") (name "unconnected-(U10A-DNU-PadAA12)") (class "Default")
      (node (ref "U10") (pin "AA12") (pinfunction "DNU_AA12") (pintype "passive+no_connect"))
    )
    (net (code "92") (name "unconnected-(U10A-DNU-PadAB1)") (class "Default")
      (node (ref "U10") (pin "AB1") (pinfunction "DNU_AB1") (pintype "passive+no_connect"))
    )
    (net (code "93") (name "unconnected-(U10A-DNU-PadAB2)") (class "Default")
      (node (ref "U10") (pin "AB2") (pinfunction "DNU_AB2") (pintype "passive+no_connect"))
    )
    (net (code "94") (name "unconnected-(U10A-DNU-PadAB11)") (class "Default")
      (node (ref "U10") (pin "AB11") (pinfunction "DNU_AB11") (pintype "passive+no_connect"))
    )
    (net (code "95") (name "unconnected-(U10A-DNU-PadAB12)") (class "Default")
      (node (ref "U10") (pin "AB12") (pinfunction "DNU_AB12") (pintype "passive+no_connect"))
    )
    (net (code "96") (name "unconnected-(U10A-DNU-PadB1)") (class "Default")
      (node (ref "U10") (pin "B1") (pinfunction "DNU_B1") (pintype "passive+no_connect"))
    )
    (net (code "97") (name "unconnected-(U10A-DNU-PadB12)") (class "Default")
      (node (ref "U10") (pin "B12") (pinfunction "DNU_B12") (pintype "passive+no_connect"))
    )
    (net (code "98") (name "unconnected-(U10A-ZQ2-PadG11)") (class "Default")
      (node (ref "U10") (pin "G11") (pinfunction "ZQ2_G11") (pintype "passive+no_connect"))
    )
  )
)
